# led_driver_schematic.net
KiCad netlist of a schematic drawn in EAGLE
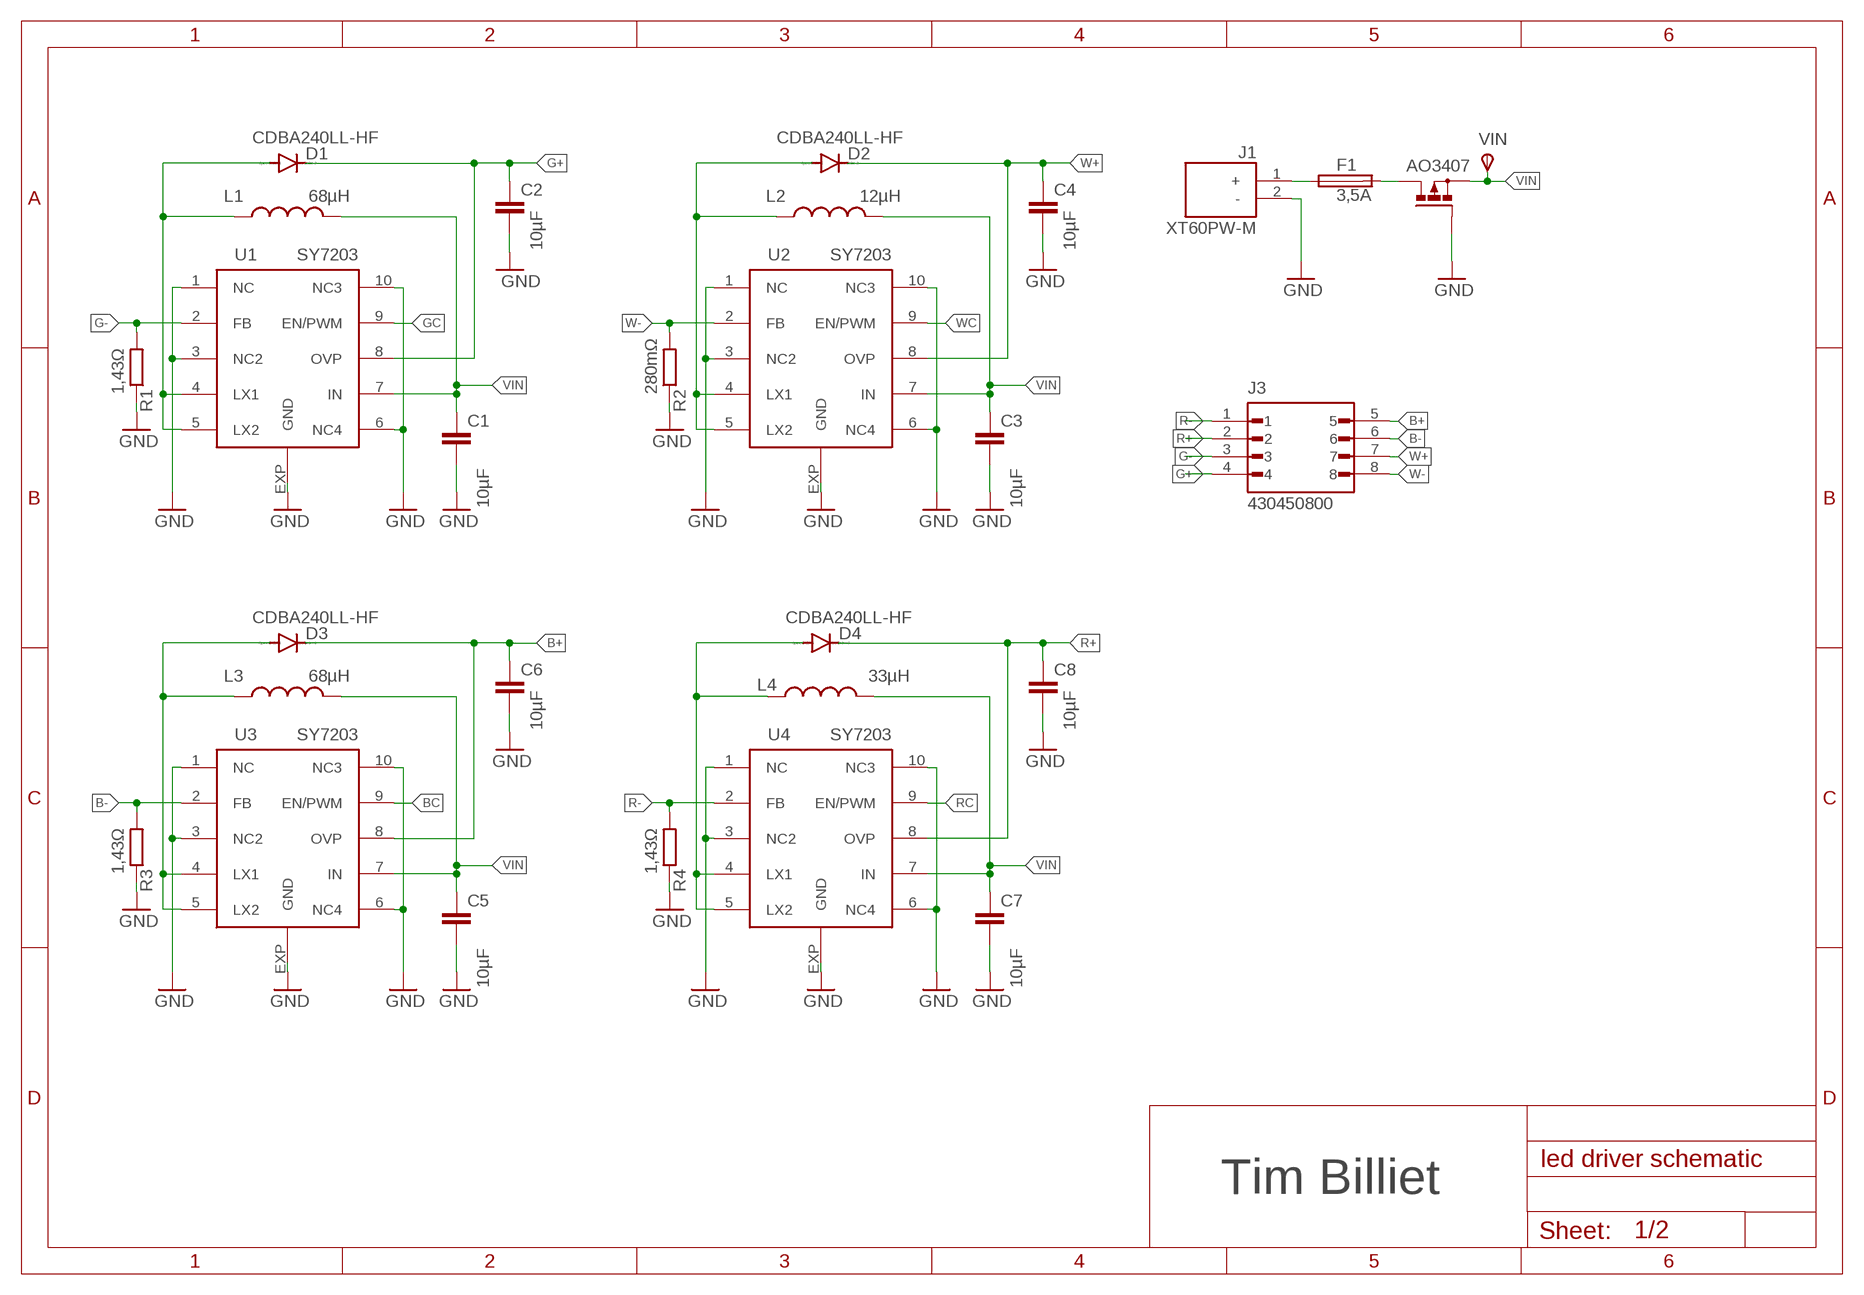
[diagram p0: schematic, sheet 1]
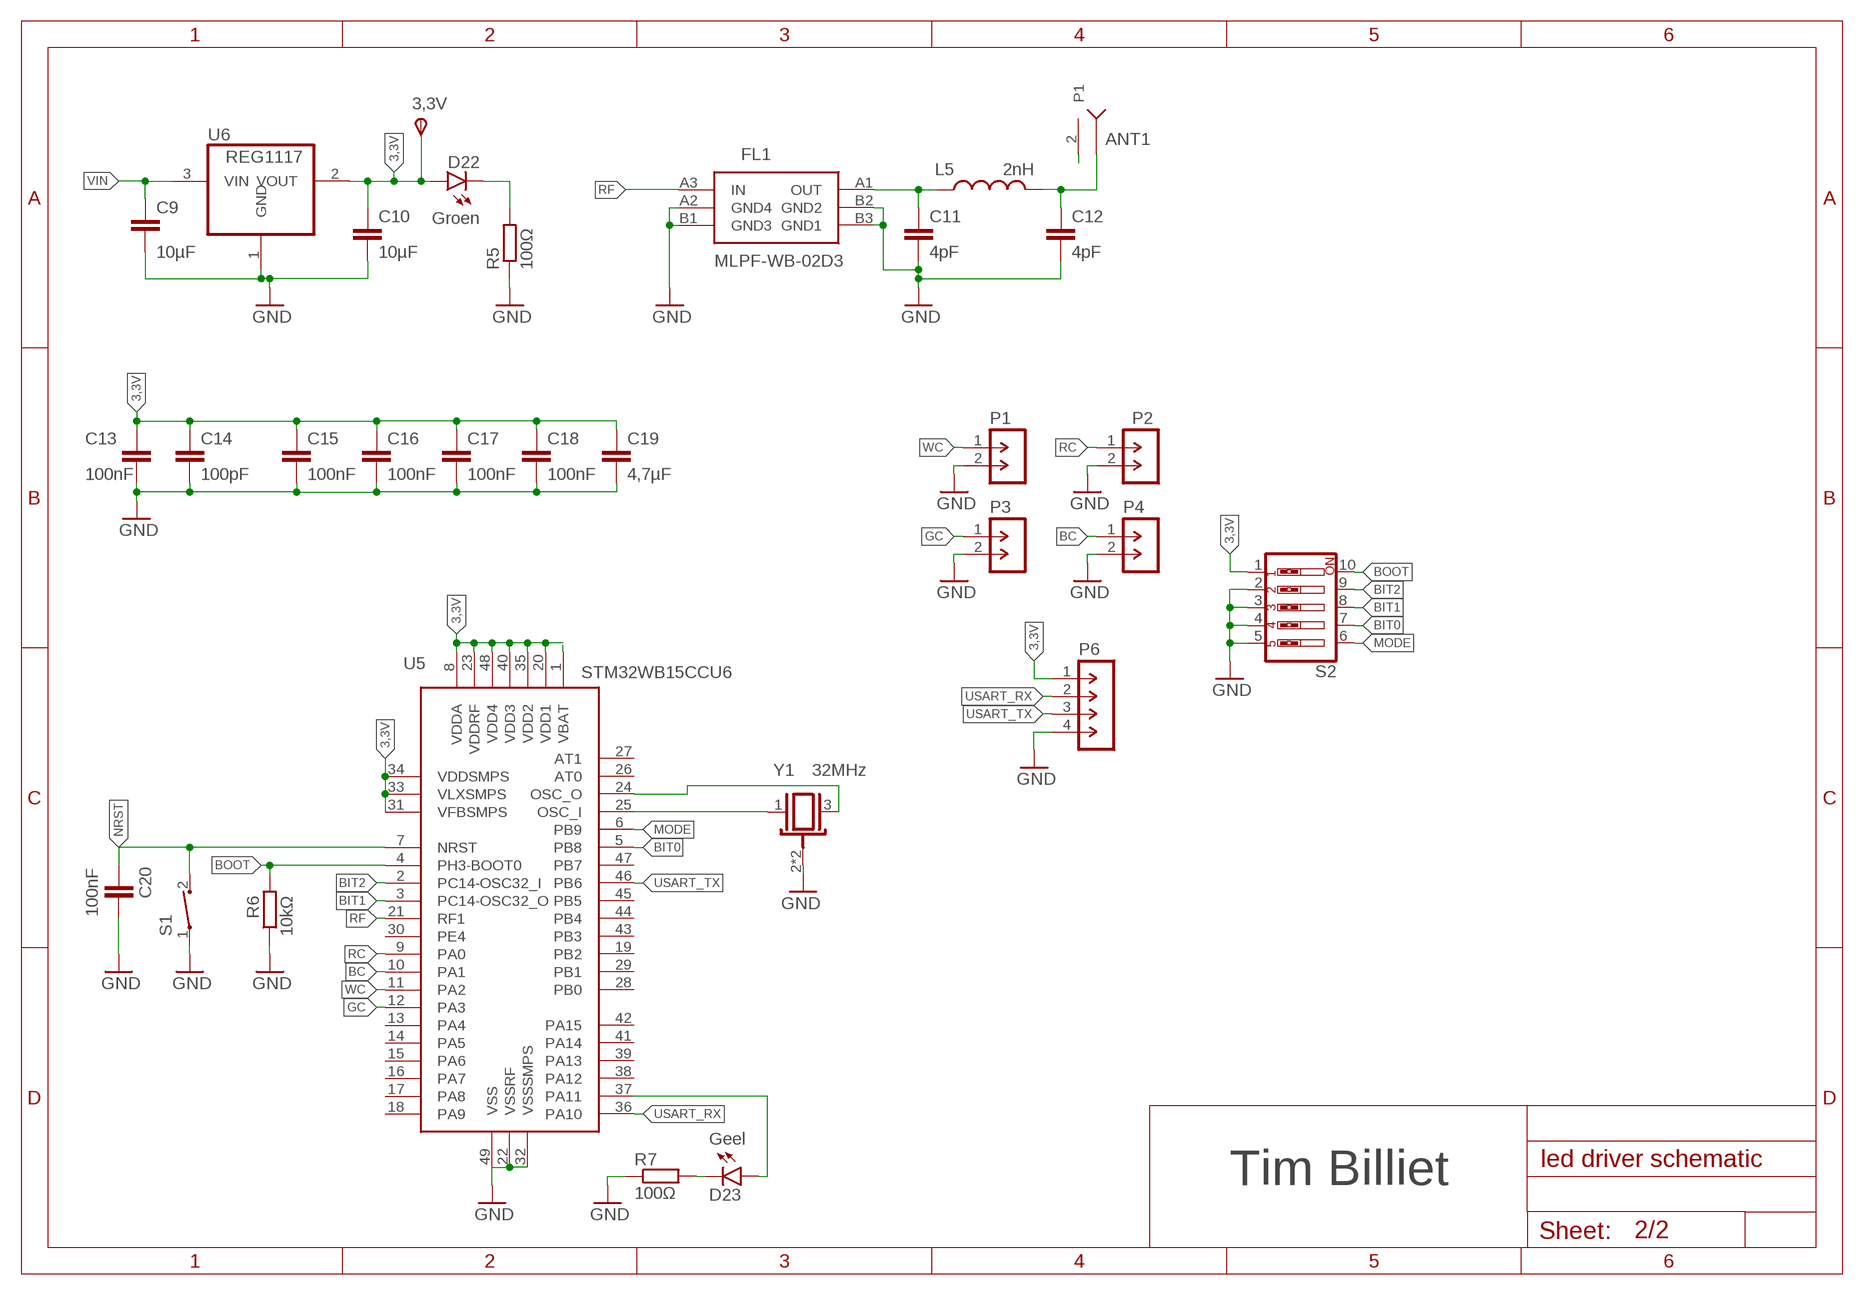
[diagram p1: schematic, sheet 2]

(export (version "E")
  (design (tool "Eeschema 10.0.6"))
  (components
    (comp (ref "3,3V")
      (value "TPSTP10R")
      (footprint "eagle-import:TP10R")
      (libsource (lib "eagle-import") (part "TPSTP10R"))
    )
    (comp (ref "ANT1")
      (value "ANT3216LL00R2400A")
      (footprint "eagle-import:ANT3216LL00R2400A")
      (libsource (lib "eagle-import") (part "ANT3216LL00R2400A"))
    )
    (comp (ref "C9")
      (value "10µF")
      (footprint "eagle-import:C0603")
      (libsource (lib "eagle-import") (part "C-EUC0603"))
    )
    (comp (ref "C10")
      (value "10µF")
      (footprint "eagle-import:C0603")
      (libsource (lib "eagle-import") (part "C-EUC0603"))
    )
    (comp (ref "C11")
      (value "4pF")
      (footprint "eagle-import:C0603")
      (libsource (lib "eagle-import") (part "C-EUC0603"))
    )
    (comp (ref "C12")
      (value "4pF")
      (footprint "eagle-import:C0603")
      (libsource (lib "eagle-import") (part "C-EUC0603"))
    )
    (comp (ref "C13")
      (value "100nF")
      (footprint "eagle-import:C0603")
      (libsource (lib "eagle-import") (part "C-EUC0603"))
    )
    (comp (ref "C14")
      (value "100pF")
      (footprint "eagle-import:C0603")
      (libsource (lib "eagle-import") (part "C-EUC0603"))
    )
    (comp (ref "C15")
      (value "100nF")
      (footprint "eagle-import:C0603")
      (libsource (lib "eagle-import") (part "C-EUC0603"))
    )
    (comp (ref "C16")
      (value "100nF")
      (footprint "eagle-import:C0603")
      (libsource (lib "eagle-import") (part "C-EUC0603"))
    )
    (comp (ref "C17")
      (value "100nF")
      (footprint "eagle-import:C0603")
      (libsource (lib "eagle-import") (part "C-EUC0603"))
    )
    (comp (ref "C18")
      (value "100nF")
      (footprint "eagle-import:C0603")
      (libsource (lib "eagle-import") (part "C-EUC0603"))
    )
    (comp (ref "C19")
      (value "4,7µF")
      (footprint "eagle-import:C0603")
      (libsource (lib "eagle-import") (part "C-EUC0603"))
    )
    (comp (ref "C20")
      (value "100nF")
      (footprint "eagle-import:C0603")
      (libsource (lib "eagle-import") (part "C-EUC0603"))
    )
    (comp (ref "D22")
      (value "Groen")
      (footprint "eagle-import:CHIP-LED0603")
      (libsource (lib "eagle-import") (part "LEDCHIP-LED0603"))
    )
    (comp (ref "D23")
      (value "Geel")
      (footprint "eagle-import:CHIP-LED0603")
      (libsource (lib "eagle-import") (part "LEDCHIP-LED0603"))
    )
    (comp (ref "FL1")
      (value "MLPF-WB-02D3")
      (footprint "eagle-import:MLPFWB02D3")
      (fields (field (name "MOUSER_PART_NUMBER") "511-MLPF-WB-02D3"))
      (libsource (lib "eagle-import") (part "MLPF-WB-02D3"))
    )
    (comp (ref "L5")
      (value "2nH")
      (footprint "eagle-import:R0603")
      (libsource (lib "eagle-import") (part "0603INDUCTOR"))
    )
    (comp (ref "P1")
      (value "M-1X02-SIP-100-32")
      (footprint "eagle-import:SIP-100-02-32")
      (libsource (lib "eagle-import") (part "M-1X02-SIP-100-32"))
    )
    (comp (ref "P2")
      (value "M-1X02-SIP-100-32")
      (footprint "eagle-import:SIP-100-02-32")
      (libsource (lib "eagle-import") (part "M-1X02-SIP-100-32"))
    )
    (comp (ref "P3")
      (value "M-1X02-SIP-100-32")
      (footprint "eagle-import:SIP-100-02-32")
      (libsource (lib "eagle-import") (part "M-1X02-SIP-100-32"))
    )
    (comp (ref "P4")
      (value "M-1X02-SIP-100-32")
      (footprint "eagle-import:SIP-100-02-32")
      (libsource (lib "eagle-import") (part "M-1X02-SIP-100-32"))
    )
    (comp (ref "P6")
      (value "M-1X04-SIP-100-32")
      (footprint "eagle-import:SIP-100-04-32")
      (libsource (lib "eagle-import") (part "M-1X04-SIP-100-32"))
    )
    (comp (ref "R5")
      (value "100Ω")
      (footprint "eagle-import:R0603")
      (libsource (lib "eagle-import") (part "R-EU_R0603"))
    )
    (comp (ref "R6")
      (value "10kΩ")
      (footprint "eagle-import:R0603")
      (libsource (lib "eagle-import") (part "R-EU_R0603"))
    )
    (comp (ref "R7")
      (value "100Ω")
      (footprint "eagle-import:R0603")
      (libsource (lib "eagle-import") (part "R-EU_R0603"))
    )
    (comp (ref "S1")
      (value "TS-1088R-02026")
      (footprint "eagle-import:TS1088R02026")
      (libsource (lib "eagle-import") (part "TS-1088R-02026"))
    )
    (comp (ref "S2")
      (value "SW_DIP-5")
      (footprint "eagle-import:EDG-05")
      (libsource (lib "eagle-import") (part "SW_DIP-5"))
    )
    (comp (ref "U5")
      (value "STM32WB15CCU6")
      (footprint "eagle-import:QFN50P700X700X60-49N")
      (libsource (lib "eagle-import") (part "STM32WB15CCU6"))
    )
    (comp (ref "U6")
      (value "REG1117")
      (footprint "eagle-import:SOT223")
      (libsource (lib "eagle-import") (part "REG1117"))
    )
    (comp (ref "Y1")
      (value "32MHz")
      (footprint "eagle-import:OSC_NX2016SA")
      (fields (field (name "MF") "NDK America, Inc.") (field (name "MP") "NX2016SA-24MHZ-EXS00A-CS10820"))
      (libsource (lib "eagle-import") (part "NX2016SA"))
    )
    (comp (ref "C1")
      (value "10µF")
      (footprint "eagle-import:C0603")
      (libsource (lib "eagle-import") (part "C-EUC0603"))
    )
    (comp (ref "C2")
      (value "10µF")
      (footprint "eagle-import:C0603")
      (libsource (lib "eagle-import") (part "C-EUC0603"))
    )
    (comp (ref "C3")
      (value "10µF")
      (footprint "eagle-import:C0603")
      (libsource (lib "eagle-import") (part "C-EUC0603"))
    )
    (comp (ref "C4")
      (value "10µF")
      (footprint "eagle-import:C0603")
      (libsource (lib "eagle-import") (part "C-EUC0603"))
    )
    (comp (ref "C5")
      (value "10µF")
      (footprint "eagle-import:C0603")
      (libsource (lib "eagle-import") (part "C-EUC0603"))
    )
    (comp (ref "C6")
      (value "10µF")
      (footprint "eagle-import:C0603")
      (libsource (lib "eagle-import") (part "C-EUC0603"))
    )
    (comp (ref "C7")
      (value "10µF")
      (footprint "eagle-import:C0603")
      (libsource (lib "eagle-import") (part "C-EUC0603"))
    )
    (comp (ref "C8")
      (value "10µF")
      (footprint "eagle-import:C0603")
      (libsource (lib "eagle-import") (part "C-EUC0603"))
    )
    (comp (ref "D1")
      (value "CDBA240LL-HF")
      (footprint "eagle-import:DO-214AC")
      (libsource (lib "eagle-import") (part "DIODE-DO-214AC"))
    )
    (comp (ref "D2")
      (value "CDBA240LL-HF")
      (footprint "eagle-import:DO-214AC")
      (libsource (lib "eagle-import") (part "DIODE-DO-214AC"))
    )
    (comp (ref "D3")
      (value "CDBA240LL-HF")
      (footprint "eagle-import:DO-214AC")
      (libsource (lib "eagle-import") (part "DIODE-DO-214AC"))
    )
    (comp (ref "D4")
      (value "CDBA240LL-HF")
      (footprint "eagle-import:DO-214AC")
      (libsource (lib "eagle-import") (part "DIODE-DO-214AC"))
    )
    (comp (ref "F1")
      (value "3,5A")
      (footprint "eagle-import:R0603")
      (libsource (lib "eagle-import") (part "0603FUSE0603"))
    )
    (comp (ref "J1")
      (value "XT60PW-M")
      (footprint "eagle-import:AMASS_XT60PW-M")
      (fields (field (name "MF") "AMASS"))
      (libsource (lib "eagle-import") (part "XT60PW-M"))
    )
    (comp (ref "J3")
      (value "430450800")
      (footprint "eagle-import:MOLEX_430450800")
      (fields (field (name "MF") "Molex") (field (name "MP") "43045-0800"))
      (libsource (lib "eagle-import") (part "430450800"))
    )
    (comp (ref "L1")
      (value "68µH")
      (footprint "eagle-import:MBH125")
      (libsource (lib "eagle-import") (part "MBH125"))
    )
    (comp (ref "L2")
      (value "12µH")
      (footprint "eagle-import:MS127-120MT")
      (libsource (lib "eagle-import") (part "MS127"))
    )
    (comp (ref "L3")
      (value "68µH")
      (footprint "eagle-import:MBH125")
      (libsource (lib "eagle-import") (part "MBH125"))
    )
    (comp (ref "L4")
      (value "33µH")
      (footprint "eagle-import:MS127-120MT")
      (libsource (lib "eagle-import") (part "MS127"))
    )
    (comp (ref "Q1")
      (value "AO3407")
      (footprint "eagle-import:SOT23")
      (libsource (lib "eagle-import") (part "AO3407SOT23"))
    )
    (comp (ref "R1")
      (value "1,43Ω")
      (footprint "eagle-import:R0805")
      (libsource (lib "eagle-import") (part "R-EU_R0805"))
    )
    (comp (ref "R2")
      (value "280mΩ")
      (footprint "eagle-import:R0805")
      (libsource (lib "eagle-import") (part "R-EU_R0805"))
    )
    (comp (ref "R3")
      (value "1,43Ω")
      (footprint "eagle-import:R0805")
      (libsource (lib "eagle-import") (part "R-EU_R0805"))
    )
    (comp (ref "R4")
      (value "1,43Ω")
      (footprint "eagle-import:R0805")
      (libsource (lib "eagle-import") (part "R-EU_R0805"))
    )
    (comp (ref "U1")
      (value "SY7203")
      (footprint "eagle-import:DFN10-3X3")
      (libsource (lib "eagle-import") (part "SY7203DBC"))
    )
    (comp (ref "U2")
      (value "SY7203")
      (footprint "eagle-import:DFN10-3X3")
      (libsource (lib "eagle-import") (part "SY7203DBC"))
    )
    (comp (ref "U3")
      (value "SY7203")
      (footprint "eagle-import:DFN10-3X3")
      (libsource (lib "eagle-import") (part "SY7203DBC"))
    )
    (comp (ref "U4")
      (value "SY7203")
      (footprint "eagle-import:DFN10-3X3")
      (libsource (lib "eagle-import") (part "SY7203DBC"))
    )
    (comp (ref "VIN")
      (value "TPSTP10R")
      (footprint "eagle-import:TP10R")
      (libsource (lib "eagle-import") (part "TPSTP10R"))
    )
  )
  (nets
    (net (code "1") (name "3,3V") (class "Default")
      (node (ref "3,3V") (pin "TP") (pinfunction "PP_TP") (pintype "input"))
      (node (ref "C10") (pin "1") (pinfunction "1_1") (pintype "passive"))
      (node (ref "C13") (pin "1") (pinfunction "1_1") (pintype "passive"))
      (node (ref "C14") (pin "1") (pinfunction "1_1") (pintype "passive"))
      (node (ref "C15") (pin "1") (pinfunction "1_1") (pintype "passive"))
      (node (ref "C16") (pin "1") (pinfunction "1_1") (pintype "passive"))
      (node (ref "C17") (pin "1") (pinfunction "1_1") (pintype "passive"))
      (node (ref "C18") (pin "1") (pinfunction "1_1") (pintype "passive"))
      (node (ref "C19") (pin "1") (pinfunction "1_1") (pintype "passive"))
      (node (ref "D22") (pin "A") (pinfunction "A_A") (pintype "passive"))
      (node (ref "P6") (pin "1") (pinfunction "1_1") (pintype "passive"))
      (node (ref "S2") (pin "1") (pinfunction "1_1") (pintype "passive"))
      (node (ref "U5") (pin "1") (pinfunction "VBAT_1") (pintype "bidirectional"))
      (node (ref "U5") (pin "20") (pinfunction "VDD1_20") (pintype "bidirectional"))
      (node (ref "U5") (pin "23") (pinfunction "VDDRF_23") (pintype "bidirectional"))
      (node (ref "U5") (pin "31") (pinfunction "VFBSMPS_31") (pintype "bidirectional"))
      (node (ref "U5") (pin "33") (pinfunction "VLXSMPS_33") (pintype "bidirectional"))
      (node (ref "U5") (pin "34") (pinfunction "VDDSMPS_34") (pintype "bidirectional"))
      (node (ref "U5") (pin "35") (pinfunction "VDD2_35") (pintype "bidirectional"))
      (node (ref "U5") (pin "40") (pinfunction "VDD3_40") (pintype "bidirectional"))
      (node (ref "U5") (pin "48") (pinfunction "VDD4_48") (pintype "bidirectional"))
      (node (ref "U5") (pin "8") (pinfunction "VDDA_8") (pintype "bidirectional"))
      (node (ref "U6") (pin "2") (pinfunction "VOUT_2") (pintype "output"))
    )
    (net (code "2") (name "B+") (class "Default")
      (node (ref "C6") (pin "1") (pinfunction "1_1") (pintype "passive"))
      (node (ref "D3") (pin "C") (pinfunction "C_C") (pintype "passive"))
      (node (ref "J3") (pin "5") (pinfunction "5_5") (pintype "passive"))
      (node (ref "U3") (pin "8") (pinfunction "OVP_8") (pintype "bidirectional"))
    )
    (net (code "3") (name "B-") (class "Default")
      (node (ref "J3") (pin "6") (pinfunction "6_6") (pintype "passive"))
      (node (ref "R3") (pin "2") (pinfunction "2_2") (pintype "passive"))
      (node (ref "U3") (pin "2") (pinfunction "FB_2") (pintype "bidirectional"))
    )
    (net (code "4") (name "BC") (class "Default")
      (node (ref "P4") (pin "1") (pinfunction "1_1") (pintype "passive"))
      (node (ref "U3") (pin "9") (pinfunction "EN/PWM_9") (pintype "bidirectional"))
      (node (ref "U5") (pin "10") (pinfunction "PA1_10") (pintype "bidirectional"))
    )
    (net (code "5") (name "BIT0") (class "Default")
      (node (ref "S2") (pin "7") (pinfunction "7_7") (pintype "passive"))
      (node (ref "U5") (pin "5") (pinfunction "PB8_5") (pintype "bidirectional"))
    )
    (net (code "6") (name "BIT1") (class "Default")
      (node (ref "S2") (pin "8") (pinfunction "8_8") (pintype "passive"))
      (node (ref "U5") (pin "3") (pinfunction "PC14-OSC32_O_3") (pintype "bidirectional"))
    )
    (net (code "7") (name "BIT2") (class "Default")
      (node (ref "S2") (pin "9") (pinfunction "9_9") (pintype "passive"))
      (node (ref "U5") (pin "2") (pinfunction "PC14-OSC32_I_2") (pintype "bidirectional"))
    )
    (net (code "8") (name "BOOT") (class "Default")
      (node (ref "R6") (pin "2") (pinfunction "2_2") (pintype "passive"))
      (node (ref "S2") (pin "10") (pinfunction "10_10") (pintype "passive"))
      (node (ref "U5") (pin "4") (pinfunction "PH3-BOOT0_4") (pintype "bidirectional"))
    )
    (net (code "9") (name "G+") (class "Default")
      (node (ref "C2") (pin "1") (pinfunction "1_1") (pintype "passive"))
      (node (ref "D1") (pin "C") (pinfunction "C_C") (pintype "passive"))
      (node (ref "J3") (pin "4") (pinfunction "4_4") (pintype "passive"))
      (node (ref "U1") (pin "8") (pinfunction "OVP_8") (pintype "bidirectional"))
    )
    (net (code "10") (name "G-") (class "Default")
      (node (ref "J3") (pin "3") (pinfunction "3_3") (pintype "passive"))
      (node (ref "R1") (pin "2") (pinfunction "2_2") (pintype "passive"))
      (node (ref "U1") (pin "2") (pinfunction "FB_2") (pintype "bidirectional"))
    )
    (net (code "11") (name "GC") (class "Default")
      (node (ref "P3") (pin "1") (pinfunction "1_1") (pintype "passive"))
      (node (ref "U1") (pin "9") (pinfunction "EN/PWM_9") (pintype "bidirectional"))
      (node (ref "U5") (pin "12") (pinfunction "PA3_12") (pintype "bidirectional"))
    )
    (net (code "12") (name "GND") (class "Default")
      (node (ref "C1") (pin "2") (pinfunction "2_2") (pintype "passive"))
      (node (ref "C10") (pin "2") (pinfunction "2_2") (pintype "passive"))
      (node (ref "C11") (pin "2") (pinfunction "2_2") (pintype "passive"))
      (node (ref "C12") (pin "2") (pinfunction "2_2") (pintype "passive"))
      (node (ref "C13") (pin "2") (pinfunction "2_2") (pintype "passive"))
      (node (ref "C14") (pin "2") (pinfunction "2_2") (pintype "passive"))
      (node (ref "C15") (pin "2") (pinfunction "2_2") (pintype "passive"))
      (node (ref "C16") (pin "2") (pinfunction "2_2") (pintype "passive"))
      (node (ref "C17") (pin "2") (pinfunction "2_2") (pintype "passive"))
      (node (ref "C18") (pin "2") (pinfunction "2_2") (pintype "passive"))
      (node (ref "C19") (pin "2") (pinfunction "2_2") (pintype "passive"))
      (node (ref "C2") (pin "2") (pinfunction "2_2") (pintype "passive"))
      (node (ref "C20") (pin "1") (pinfunction "1_1") (pintype "passive"))
      (node (ref "C3") (pin "2") (pinfunction "2_2") (pintype "passive"))
      (node (ref "C4") (pin "2") (pinfunction "2_2") (pintype "passive"))
      (node (ref "C5") (pin "2") (pinfunction "2_2") (pintype "passive"))
      (node (ref "C6") (pin "2") (pinfunction "2_2") (pintype "passive"))
      (node (ref "C7") (pin "2") (pinfunction "2_2") (pintype "passive"))
      (node (ref "C8") (pin "2") (pinfunction "2_2") (pintype "passive"))
      (node (ref "C9") (pin "2") (pinfunction "2_2") (pintype "passive"))
      (node (ref "FL1") (pin "A2") (pinfunction "GND4_A2") (pintype "bidirectional"))
      (node (ref "FL1") (pin "B1") (pinfunction "GND3_B1") (pintype "bidirectional"))
      (node (ref "FL1") (pin "B2") (pinfunction "GND2_B2") (pintype "bidirectional"))
      (node (ref "FL1") (pin "B3") (pinfunction "GND1_B3") (pintype "bidirectional"))
      (node (ref "J1") (pin "2") (pinfunction "-_2") (pintype "passive"))
      (node (ref "P1") (pin "2") (pinfunction "2_2") (pintype "passive"))
      (node (ref "P2") (pin "2") (pinfunction "2_2") (pintype "passive"))
      (node (ref "P3") (pin "2") (pinfunction "2_2") (pintype "passive"))
      (node (ref "P4") (pin "2") (pinfunction "2_2") (pintype "passive"))
      (node (ref "P6") (pin "4") (pinfunction "4_4") (pintype "passive"))
      (node (ref "Q1") (pin "1") (pinfunction "G_1") (pintype "passive"))
      (node (ref "R1") (pin "1") (pinfunction "1_1") (pintype "passive"))
      (node (ref "R2") (pin "1") (pinfunction "1_1") (pintype "passive"))
      (node (ref "R3") (pin "1") (pinfunction "1_1") (pintype "passive"))
      (node (ref "R4") (pin "1") (pinfunction "1_1") (pintype "passive"))
      (node (ref "R5") (pin "1") (pinfunction "1_1") (pintype "passive"))
      (node (ref "R6") (pin "1") (pinfunction "1_1") (pintype "passive"))
      (node (ref "R7") (pin "1") (pinfunction "1_1") (pintype "passive"))
      (node (ref "S1") (pin "1") (pinfunction "1_1") (pintype "passive"))
      (node (ref "S2") (pin "2") (pinfunction "2_2") (pintype "passive"))
      (node (ref "S2") (pin "3") (pinfunction "3_3") (pintype "passive"))
      (node (ref "S2") (pin "4") (pinfunction "4_4") (pintype "passive"))
      (node (ref "S2") (pin "5") (pinfunction "5_5") (pintype "passive"))
      (node (ref "U1") (pin "1") (pinfunction "NC_1") (pintype "bidirectional"))
      (node (ref "U1") (pin "10") (pinfunction "NC3_10") (pintype "bidirectional"))
      (node (ref "U1") (pin "3") (pinfunction "NC2_3") (pintype "bidirectional"))
      (node (ref "U1") (pin "6") (pinfunction "NC4_6") (pintype "bidirectional"))
      (node (ref "U1") (pin "EXP") (pinfunction "GND_EXP") (pintype "bidirectional"))
      (node (ref "U2") (pin "1") (pinfunction "NC_1") (pintype "bidirectional"))
      (node (ref "U2") (pin "10") (pinfunction "NC3_10") (pintype "bidirectional"))
      (node (ref "U2") (pin "3") (pinfunction "NC2_3") (pintype "bidirectional"))
      (node (ref "U2") (pin "6") (pinfunction "NC4_6") (pintype "bidirectional"))
      (node (ref "U2") (pin "EXP") (pinfunction "GND_EXP") (pintype "bidirectional"))
      (node (ref "U3") (pin "1") (pinfunction "NC_1") (pintype "bidirectional"))
      (node (ref "U3") (pin "10") (pinfunction "NC3_10") (pintype "bidirectional"))
      (node (ref "U3") (pin "3") (pinfunction "NC2_3") (pintype "bidirectional"))
      (node (ref "U3") (pin "6") (pinfunction "NC4_6") (pintype "bidirectional"))
      (node (ref "U3") (pin "EXP") (pinfunction "GND_EXP") (pintype "bidirectional"))
      (node (ref "U4") (pin "1") (pinfunction "NC_1") (pintype "bidirectional"))
      (node (ref "U4") (pin "10") (pinfunction "NC3_10") (pintype "bidirectional"))
      (node (ref "U4") (pin "3") (pinfunction "NC2_3") (pintype "bidirectional"))
      (node (ref "U4") (pin "6") (pinfunction "NC4_6") (pintype "bidirectional"))
      (node (ref "U4") (pin "EXP") (pinfunction "GND_EXP") (pintype "bidirectional"))
      (node (ref "U5") (pin "22") (pinfunction "VSSRF_22") (pintype "bidirectional"))
      (node (ref "U5") (pin "32") (pinfunction "VSSSMPS_32") (pintype "bidirectional"))
      (node (ref "U5") (pin "49") (pinfunction "VSS_49") (pintype "power_in"))
      (node (ref "U6") (pin "1") (pinfunction "GND_1") (pintype "power_in"))
      (node (ref "Y1") (pin "2") (pinfunction "GND_2") (pintype "power_in"))
      (node (ref "Y1") (pin "4") (pinfunction "GND_4") (pintype "power_in"))
    )
    (net (code "13") (name "MODE") (class "Default")
      (node (ref "S2") (pin "6") (pinfunction "6_6") (pintype "passive"))
      (node (ref "U5") (pin "6") (pinfunction "PB9_6") (pintype "bidirectional"))
    )
    (net (code "14") (name "NRST") (class "Default")
      (node (ref "C20") (pin "2") (pinfunction "2_2") (pintype "passive"))
      (node (ref "S1") (pin "2") (pinfunction "2_2") (pintype "passive"))
      (node (ref "U5") (pin "7") (pinfunction "NRST_7") (pintype "bidirectional"))
    )
    (net (code "15") (name "Net-(ANT1-ANTENNA)") (class "Default")
      (node (ref "ANT1") (pin "1") (pinfunction "ANTENNA_1") (pintype "input"))
      (node (ref "C12") (pin "1") (pinfunction "1_1") (pintype "passive"))
      (node (ref "L5") (pin "2") (pinfunction "2_2") (pintype "passive"))
    )
    (net (code "16") (name "Net-(D22-PadC)") (class "Default")
      (node (ref "D22") (pin "C") (pinfunction "C_C") (pintype "passive"))
      (node (ref "R5") (pin "2") (pinfunction "2_2") (pintype "passive"))
    )
    (net (code "17") (name "Net-(D23-PadC)") (class "Default")
      (node (ref "D23") (pin "C") (pinfunction "C_C") (pintype "passive"))
      (node (ref "R7") (pin "2") (pinfunction "2_2") (pintype "passive"))
    )
    (net (code "18") (name "Net-(FL1-OUT)") (class "Default")
      (node (ref "C11") (pin "1") (pinfunction "1_1") (pintype "passive"))
      (node (ref "FL1") (pin "A1") (pinfunction "OUT_A1") (pintype "bidirectional"))
      (node (ref "L5") (pin "1") (pinfunction "1_1") (pintype "passive"))
    )
    (net (code "19") (name "Net-(J1-+)") (class "Default")
      (node (ref "F1") (pin "1") (pinfunction "1_1") (pintype "passive"))
      (node (ref "J1") (pin "1") (pinfunction "+_1") (pintype "passive"))
    )
    (net (code "20") (name "Net-(L1-1)") (class "Default")
      (node (ref "D1") (pin "A") (pinfunction "A_A") (pintype "passive"))
      (node (ref "L1") (pin "P$1") (pinfunction "1_P$1") (pintype "passive"))
      (node (ref "U1") (pin "4") (pinfunction "LX1_4") (pintype "bidirectional"))
      (node (ref "U1") (pin "5") (pinfunction "LX2_5") (pintype "bidirectional"))
    )
    (net (code "21") (name "Net-(L2-1)") (class "Default")
      (node (ref "D2") (pin "A") (pinfunction "A_A") (pintype "passive"))
      (node (ref "L2") (pin "P$1") (pinfunction "1_P$1") (pintype "passive"))
      (node (ref "U2") (pin "4") (pinfunction "LX1_4") (pintype "bidirectional"))
      (node (ref "U2") (pin "5") (pinfunction "LX2_5") (pintype "bidirectional"))
    )
    (net (code "22") (name "Net-(L3-1)") (class "Default")
      (node (ref "D3") (pin "A") (pinfunction "A_A") (pintype "passive"))
      (node (ref "L3") (pin "P$1") (pinfunction "1_P$1") (pintype "passive"))
      (node (ref "U3") (pin "4") (pinfunction "LX1_4") (pintype "bidirectional"))
      (node (ref "U3") (pin "5") (pinfunction "LX2_5") (pintype "bidirectional"))
    )
    (net (code "23") (name "Net-(L4-1)") (class "Default")
      (node (ref "D4") (pin "A") (pinfunction "A_A") (pintype "passive"))
      (node (ref "L4") (pin "P$1") (pinfunction "1_P$1") (pintype "passive"))
      (node (ref "U4") (pin "4") (pinfunction "LX1_4") (pintype "bidirectional"))
      (node (ref "U4") (pin "5") (pinfunction "LX2_5") (pintype "bidirectional"))
    )
    (net (code "24") (name "Net-(Q1-D)") (class "Default")
      (node (ref "F1") (pin "2") (pinfunction "2_2") (pintype "passive"))
      (node (ref "Q1") (pin "3") (pinfunction "D_3") (pintype "passive"))
    )
    (net (code "25") (name "Net-(U5-OSC_I)") (class "Default")
      (node (ref "U5") (pin "25") (pinfunction "OSC_I_25") (pintype "bidirectional"))
      (node (ref "Y1") (pin "1") (pinfunction "1_1") (pintype "passive"))
    )
    (net (code "26") (name "Net-(U5-OSC_O)") (class "Default")
      (node (ref "U5") (pin "24") (pinfunction "OSC_O_24") (pintype "bidirectional"))
      (node (ref "Y1") (pin "3") (pinfunction "3_3") (pintype "passive"))
    )
    (net (code "27") (name "Net-(U5-PA11)") (class "Default")
      (node (ref "D23") (pin "A") (pinfunction "A_A") (pintype "passive"))
      (node (ref "U5") (pin "37") (pinfunction "PA11_37") (pintype "bidirectional"))
    )
    (net (code "28") (name "R+") (class "Default")
      (node (ref "C8") (pin "1") (pinfunction "1_1") (pintype "passive"))
      (node (ref "D4") (pin "C") (pinfunction "C_C") (pintype "passive"))
      (node (ref "J3") (pin "2") (pinfunction "2_2") (pintype "passive"))
      (node (ref "U4") (pin "8") (pinfunction "OVP_8") (pintype "bidirectional"))
    )
    (net (code "29") (name "R-") (class "Default")
      (node (ref "J3") (pin "1") (pinfunction "1_1") (pintype "passive"))
      (node (ref "R4") (pin "2") (pinfunction "2_2") (pintype "passive"))
      (node (ref "U4") (pin "2") (pinfunction "FB_2") (pintype "bidirectional"))
    )
    (net (code "30") (name "RC") (class "Default")
      (node (ref "P2") (pin "1") (pinfunction "1_1") (pintype "passive"))
      (node (ref "U4") (pin "9") (pinfunction "EN/PWM_9") (pintype "bidirectional"))
      (node (ref "U5") (pin "9") (pinfunction "PA0_9") (pintype "bidirectional"))
    )
    (net (code "31") (name "RF") (class "Default")
      (node (ref "FL1") (pin "A3") (pinfunction "IN_A3") (pintype "bidirectional"))
      (node (ref "U5") (pin "21") (pinfunction "RF1_21") (pintype "bidirectional"))
    )
    (net (code "32") (name "USART_RX") (class "Default")
      (node (ref "P6") (pin "2") (pinfunction "2_2") (pintype "passive"))
      (node (ref "U5") (pin "36") (pinfunction "PA10_36") (pintype "bidirectional"))
    )
    (net (code "33") (name "USART_TX") (class "Default")
      (node (ref "P6") (pin "3") (pinfunction "3_3") (pintype "passive"))
      (node (ref "U5") (pin "46") (pinfunction "PB6_46") (pintype "bidirectional"))
    )
    (net (code "34") (name "VIN") (class "Default")
      (node (ref "C1") (pin "1") (pinfunction "1_1") (pintype "passive"))
      (node (ref "C3") (pin "1") (pinfunction "1_1") (pintype "passive"))
      (node (ref "C5") (pin "1") (pinfunction "1_1") (pintype "passive"))
      (node (ref "C7") (pin "1") (pinfunction "1_1") (pintype "passive"))
      (node (ref "C9") (pin "1") (pinfunction "1_1") (pintype "passive"))
      (node (ref "L1") (pin "P$2") (pinfunction "2_P$2") (pintype "passive"))
      (node (ref "L2") (pin "P$2") (pinfunction "2_P$2") (pintype "passive"))
      (node (ref "L3") (pin "P$2") (pinfunction "2_P$2") (pintype "passive"))
      (node (ref "L4") (pin "P$2") (pinfunction "2_P$2") (pintype "passive"))
      (node (ref "Q1") (pin "2") (pinfunction "S_2") (pintype "passive"))
      (node (ref "U1") (pin "7") (pinfunction "IN_7") (pintype "power_in"))
      (node (ref "U2") (pin "7") (pinfunction "IN_7") (pintype "power_in"))
      (node (ref "U3") (pin "7") (pinfunction "IN_7") (pintype "power_in"))
      (node (ref "U4") (pin "7") (pinfunction "IN_7") (pintype "power_in"))
      (node (ref "U6") (pin "3") (pinfunction "VIN_3") (pintype "input"))
      (node (ref "VIN") (pin "TP") (pinfunction "PP_TP") (pintype "input"))
    )
    (net (code "35") (name "W+") (class "Default")
      (node (ref "C4") (pin "1") (pinfunction "1_1") (pintype "passive"))
      (node (ref "D2") (pin "C") (pinfunction "C_C") (pintype "passive"))
      (node (ref "J3") (pin "7") (pinfunction "7_7") (pintype "passive"))
      (node (ref "U2") (pin "8") (pinfunction "OVP_8") (pintype "bidirectional"))
    )
    (net (code "36") (name "W-") (class "Default")
      (node (ref "J3") (pin "8") (pinfunction "8_8") (pintype "passive"))
      (node (ref "R2") (pin "2") (pinfunction "2_2") (pintype "passive"))
      (node (ref "U2") (pin "2") (pinfunction "FB_2") (pintype "bidirectional"))
    )
    (net (code "37") (name "WC") (class "Default")
      (node (ref "P1") (pin "1") (pinfunction "1_1") (pintype "passive"))
      (node (ref "U2") (pin "9") (pinfunction "EN/PWM_9") (pintype "bidirectional"))
      (node (ref "U5") (pin "11") (pinfunction "PA2_11") (pintype "bidirectional"))
    )
    (net (code "38") (name "unconnected-(ANT1-P1-Pad2)") (class "Default")
      (node (ref "ANT1") (pin "2") (pinfunction "P1_2") (pintype "bidirectional"))
    )
    (net (code "39") (name "unconnected-(U5-AT0-Pad26)") (class "Default")
      (node (ref "U5") (pin "26") (pinfunction "AT0_26") (pintype "bidirectional"))
    )
    (net (code "40") (name "unconnected-(U5-AT1-Pad27)") (class "Default")
      (node (ref "U5") (pin "27") (pinfunction "AT1_27") (pintype "bidirectional"))
    )
    (net (code "41") (name "unconnected-(U5-PA4-Pad13)") (class "Default")
      (node (ref "U5") (pin "13") (pinfunction "PA4_13") (pintype "bidirectional"))
    )
    (net (code "42") (name "unconnected-(U5-PA5-Pad14)") (class "Default")
      (node (ref "U5") (pin "14") (pinfunction "PA5_14") (pintype "bidirectional"))
    )
    (net (code "43") (name "unconnected-(U5-PA6-Pad15)") (class "Default")
      (node (ref "U5") (pin "15") (pinfunction "PA6_15") (pintype "bidirectional"))
    )
    (net (code "44") (name "unconnected-(U5-PA7-Pad16)") (class "Default")
      (node (ref "U5") (pin "16") (pinfunction "PA7_16") (pintype "bidirectional"))
    )
    (net (code "45") (name "unconnected-(U5-PA8-Pad17)") (class "Default")
      (node (ref "U5") (pin "17") (pinfunction "PA8_17") (pintype "bidirectional"))
    )
    (net (code "46") (name "unconnected-(U5-PA9-Pad18)") (class "Default")
      (node (ref "U5") (pin "18") (pinfunction "PA9_18") (pintype "bidirectional"))
    )
    (net (code "47") (name "unconnected-(U5-PA12-Pad38)") (class "Default")
      (node (ref "U5") (pin "38") (pinfunction "PA12_38") (pintype "bidirectional"))
    )
    (net (code "48") (name "unconnected-(U5-PA13-Pad39)") (class "Default")
      (node (ref "U5") (pin "39") (pinfunction "PA13_39") (pintype "bidirectional"))
    )
    (net (code "49") (name "unconnected-(U5-PA14-Pad41)") (class "Default")
      (node (ref "U5") (pin "41") (pinfunction "PA14_41") (pintype "bidirectional"))
    )
    (net (code "50") (name "unconnected-(U5-PA15-Pad42)") (class "Default")
      (node (ref "U5") (pin "42") (pinfunction "PA15_42") (pintype "bidirectional"))
    )
    (net (code "51") (name "unconnected-(U5-PB0-Pad28)") (class "Default")
      (node (ref "U5") (pin "28") (pinfunction "PB0_28") (pintype "bidirectional"))
    )
    (net (code "52") (name "unconnected-(U5-PB1-Pad29)") (class "Default")
      (node (ref "U5") (pin "29") (pinfunction "PB1_29") (pintype "bidirectional"))
    )
    (net (code "53") (name "unconnected-(U5-PB2-Pad19)") (class "Default")
      (node (ref "U5") (pin "19") (pinfunction "PB2_19") (pintype "bidirectional"))
    )
    (net (code "54") (name "unconnected-(U5-PB3-Pad43)") (class "Default")
      (node (ref "U5") (pin "43") (pinfunction "PB3_43") (pintype "bidirectional"))
    )
    (net (code "55") (name "unconnected-(U5-PB4-Pad44)") (class "Default")
      (node (ref "U5") (pin "44") (pinfunction "PB4_44") (pintype "bidirectional"))
    )
    (net (code "56") (name "unconnected-(U5-PB5-Pad45)") (class "Default")
      (node (ref "U5") (pin "45") (pinfunction "PB5_45") (pintype "bidirectional"))
    )
    (net (code "57") (name "unconnected-(U5-PB7-Pad47)") (class "Default")
      (node (ref "U5") (pin "47") (pinfunction "PB7_47") (pintype "bidirectional"))
    )
    (net (code "58") (name "unconnected-(U5-PE4-Pad30)") (class "Default")
      (node (ref "U5") (pin "30") (pinfunction "PE4_30") (pintype "bidirectional"))
    )
  )
)
